# AI.net
KiCad netlist of a schematic drawn in Altium Designer
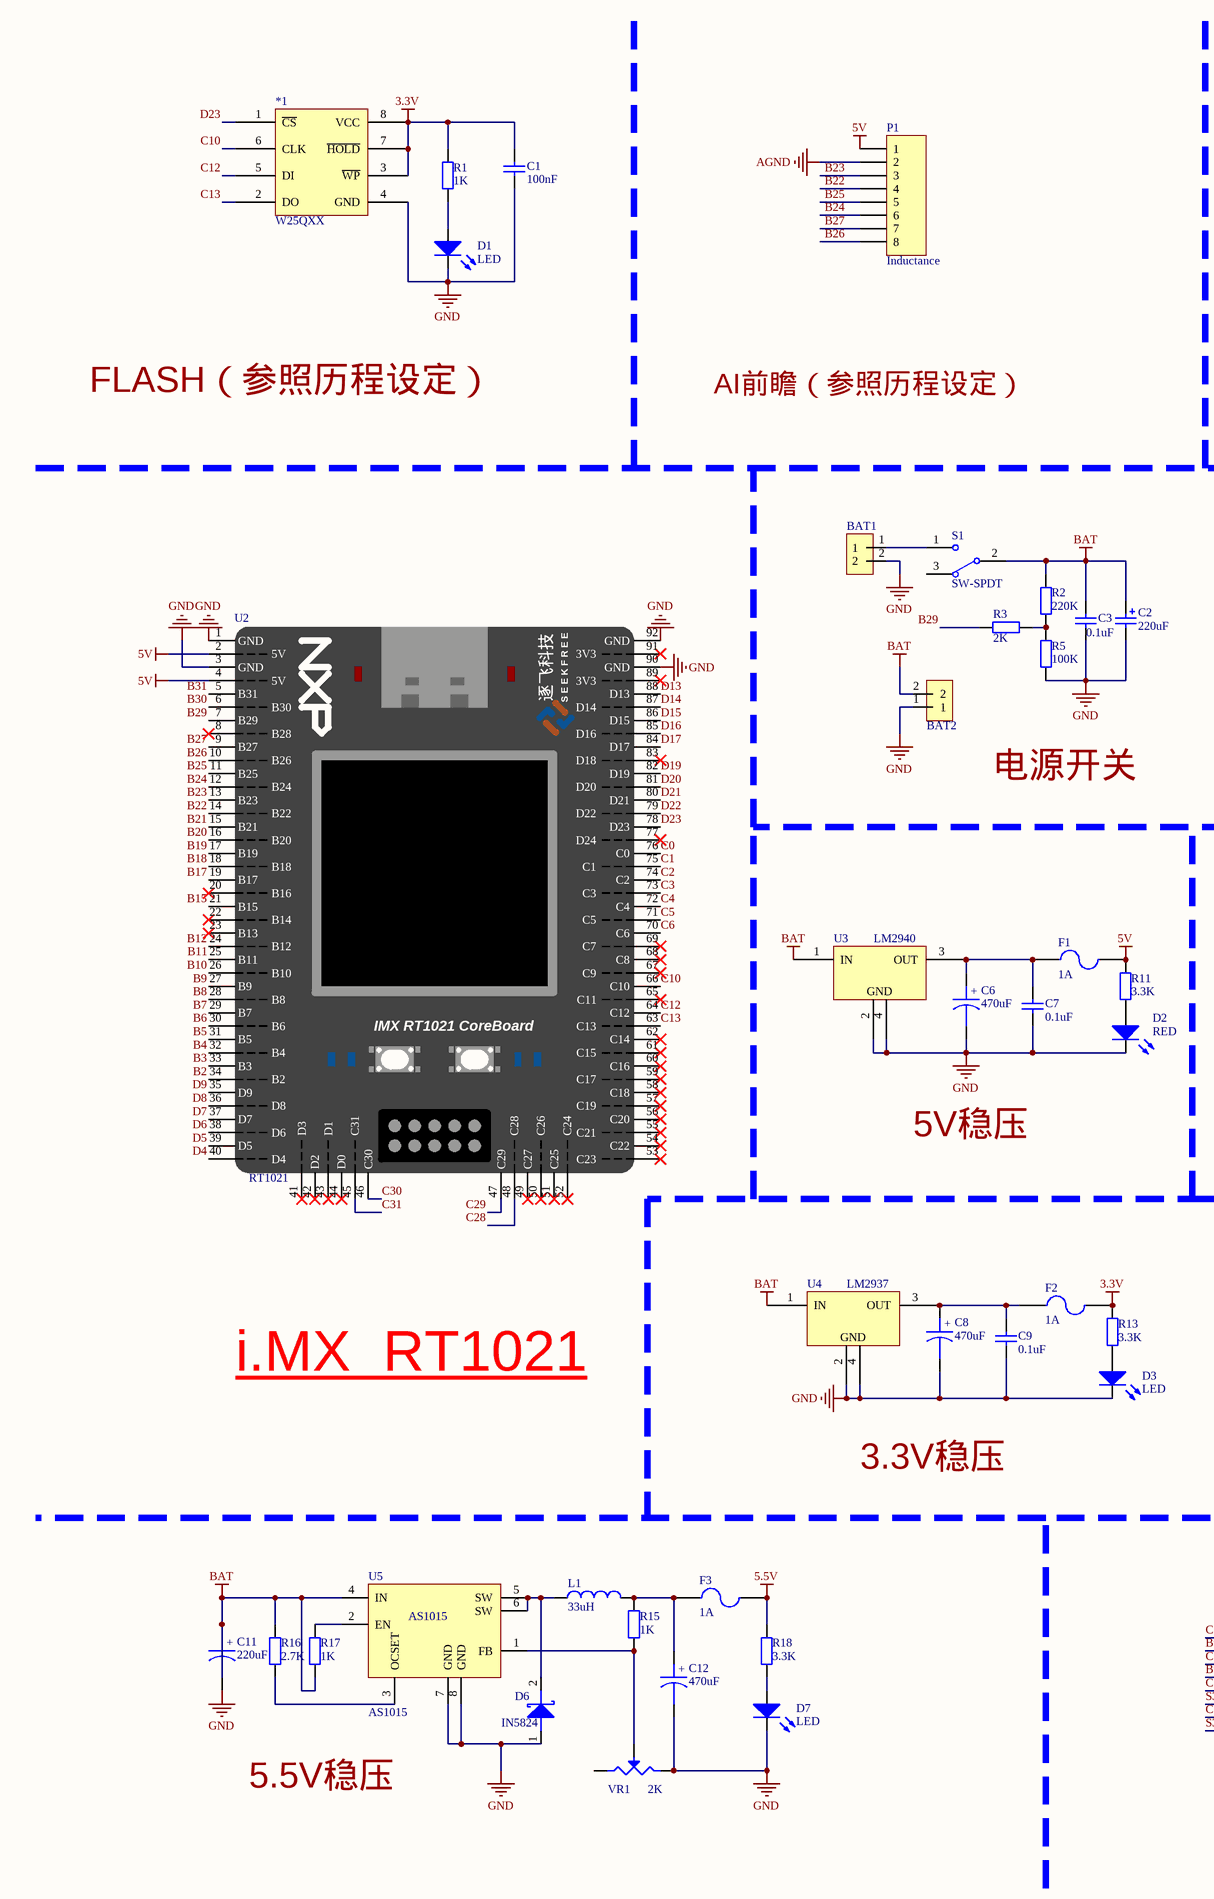
[diagram p0: AI原理图.SchDoc, left]
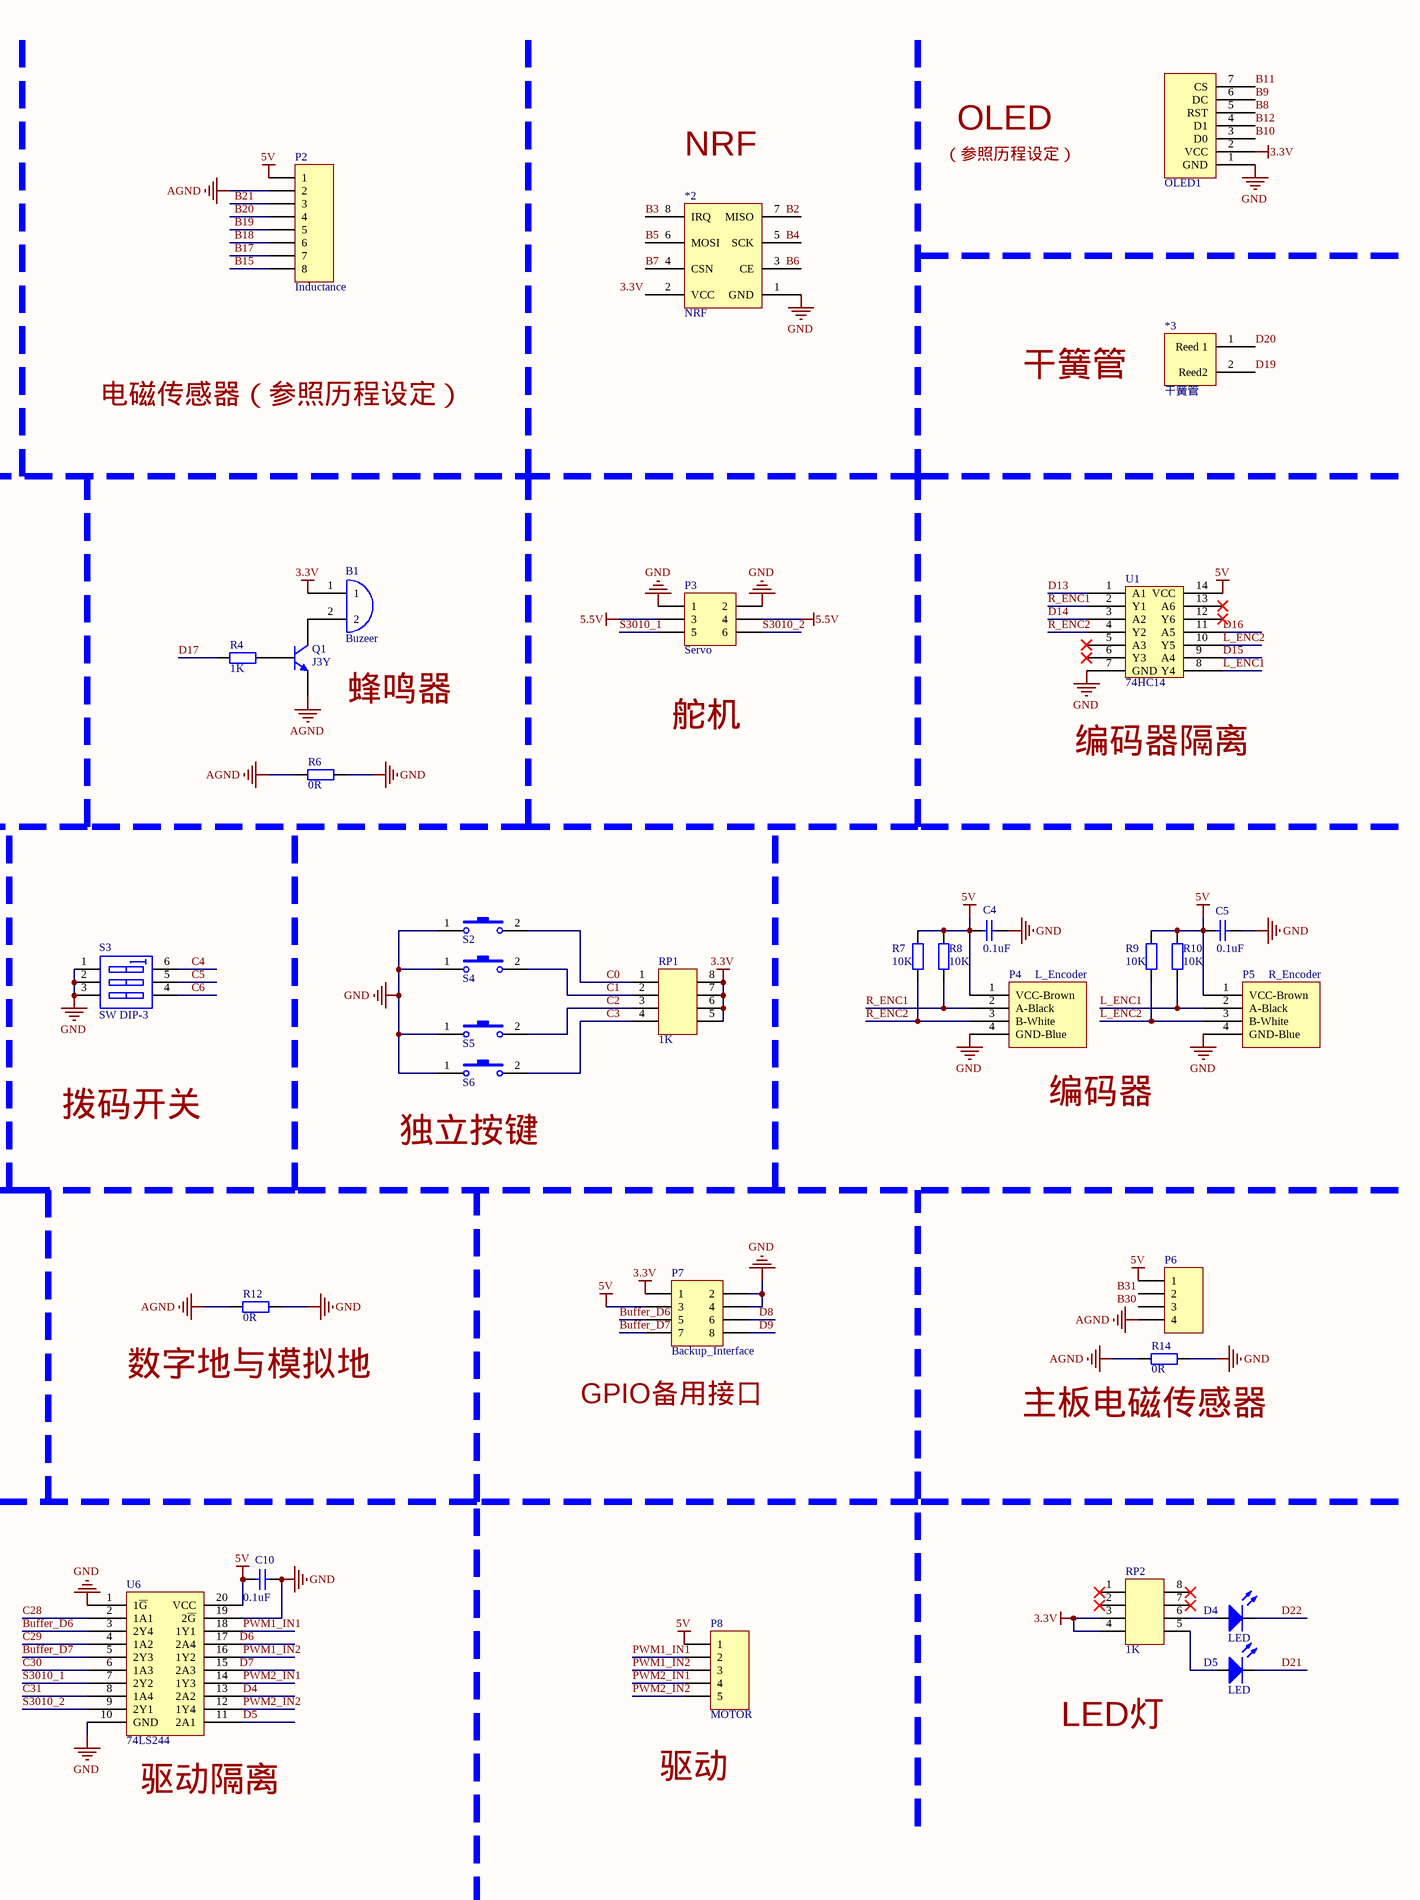
[diagram p1: AI原理图.SchDoc, right]

(export (version "E")
  (design (tool "Eeschema 10.0.6"))
  (components
    (comp (ref "*1") (value "W25QXX") (footprint "SOP8_M") (libsource (lib "红旗_SchLib_V1.0") (part "W25QXX")))
    (comp (ref "*2") (value "NRF") (footprint "HDR2X4") (libsource (lib "红旗_SchLib_V1.0") (part "NRF")))
    (comp (ref "*3") (value "干簧管") (footprint "HDR1X2") (libsource (lib "红旗_SchLib_V1.0") (part "干簧管")))
    (comp (ref "B1") (value "Buzeer") (footprint "BUZEER") (libsource (lib "红旗_SchLib") (part "Buzzer")))
    (comp (ref "BAT1")
      (value "电池")
      (footprint "PIN2")
      (description "Jumper")
      (libsource (lib "") (part "Header 2_1"))
    )
    (comp (ref "BAT2")
      (value "驱动")
      (footprint "T")
      (description "Jumper")
      (libsource (lib "红旗_SchLib") (part "Header 2"))
    )
    (comp (ref "C1")
      (value "100nF")
      (footprint "0805C")
      (description "Capacitor (Semiconductor SIM Model)")
      (fields (field (name "PUBLISHER") "Altium Limited"))
      (libsource (lib "红旗_SchLib") (part "Cap Semi"))
    )
    (comp (ref "C2")
      (value "220uF")
      (footprint "直插电解电容")
      (description "Polarized Capacitor (Radial)")
      (fields (field (name "PUBLISHER") "Altium Limited"))
      (libsource (lib "红旗_SchLib") (part "Cap Pol1"))
    )
    (comp (ref "C3")
      (value "0.1uF")
      (footprint "0805C")
      (description "Capacitor (Semiconductor SIM Model)")
      (fields (field (name "PUBLISHER") "Altium Limited"))
      (libsource (lib "红旗_SchLib") (part "Cap Semi"))
    )
    (comp (ref "C4")
      (value "0.1uF")
      (footprint "0805C")
      (description "Capacitor (Semiconductor SIM Model)")
      (fields (field (name "PUBLISHER") "Altium Limited"))
      (libsource (lib "PCB_Project2") (part "Cap Semi"))
    )
    (comp (ref "C5")
      (value "0.1uF")
      (footprint "0805C")
      (description "Capacitor (Semiconductor SIM Model)")
      (fields (field (name "PUBLISHER") "Altium Limited"))
      (libsource (lib "PCB_Project2") (part "Cap Semi"))
    )
    (comp (ref "C6")
      (value "470uF")
      (footprint "LQ_C10X10")
      (description "Capacitor")
      (libsource (lib "红旗_SchLib") (part "CAPACITOR POL"))
    )
    (comp (ref "C7")
      (value "0.1uF")
      (footprint "0805C")
      (description "Capacitor (Semiconductor SIM Model)")
      (fields (field (name "PUBLISHER") "Altium Limited"))
      (libsource (lib "红旗_SchLib") (part "Cap Semi"))
    )
    (comp (ref "C8")
      (value "470uF")
      (footprint "LQ_C10X10")
      (description "Capacitor")
      (libsource (lib "红旗_SchLib") (part "CAPACITOR POL"))
    )
    (comp (ref "C9")
      (value "0.1uF")
      (footprint "0805C")
      (description "Capacitor (Semiconductor SIM Model)")
      (fields (field (name "PUBLISHER") "Altium Limited"))
      (libsource (lib "红旗_SchLib") (part "Cap Semi"))
    )
    (comp (ref "C10")
      (value "0.1uF")
      (footprint "0805C")
      (description "Capacitor (Semiconductor SIM Model)")
      (fields (field (name "PUBLISHER") "Altium Limited"))
      (libsource (lib "PCB_Project2") (part "Cap Semi"))
    )
    (comp (ref "C11")
      (value "220uF")
      (footprint "直插电解电容")
      (description "Capacitor")
      (libsource (lib "红旗_SchLib") (part "CAPACITOR POL"))
    )
    (comp (ref "C12")
      (value "470uF")
      (footprint "LQ_C10X10")
      (description "Capacitor")
      (libsource (lib "红旗_SchLib") (part "CAPACITOR POL"))
    )
    (comp (ref "D1")
      (value "LED")
      (footprint "LED0805R")
      (description "Typical RED, GREEN, YELLOW, AMBER GaAs LED")
      (fields (field (name "PUBLISHER") "Altium Limited"))
      (libsource (lib "红旗_SchLib") (part "LED2"))
    )
    (comp (ref "D2")
      (value "RED")
      (footprint "LED0805R")
      (description "Typical RED, GREEN, YELLOW, AMBER GaAs LED")
      (fields (field (name "PUBLISHER") "Altium Limited"))
      (libsource (lib "红旗_SchLib") (part "LED2"))
    )
    (comp (ref "D3")
      (value "LED")
      (footprint "LED0805R")
      (description "Typical RED, GREEN, YELLOW, AMBER GaAs LED")
      (fields (field (name "PUBLISHER") "Altium Limited"))
      (libsource (lib "红旗_SchLib") (part "LED2"))
    )
    (comp (ref "D4")
      (value "LED")
      (footprint "LED0805R")
      (description "Typical RED, GREEN, YELLOW, AMBER GaAs LED")
      (fields (field (name "PUBLISHER") "Altium Limited"))
      (libsource (lib "红旗_SchLib") (part "LED2"))
    )
    (comp (ref "D5")
      (value "LED")
      (footprint "LED0805R")
      (description "Typical RED, GREEN, YELLOW, AMBER GaAs LED")
      (fields (field (name "PUBLISHER") "Altium Limited"))
      (libsource (lib "红旗_SchLib") (part "LED2"))
    )
    (comp (ref "D6")
      (value "IN5824")
      (footprint "SMA")
      (description "MBRA140T3")
      (libsource (lib "红旗_SchLib") (part "D-MBRA140T3"))
    )
    (comp (ref "D7")
      (value "LED")
      (footprint "LED0805R")
      (description "Typical RED, GREEN, YELLOW, AMBER GaAs LED")
      (fields (field (name "PUBLISHER") "Altium Limited"))
      (libsource (lib "红旗_SchLib") (part "LED2"))
    )
    (comp (ref "F1")
      (value "1A")
      (footprint "C1206")
      (description "Fuse")
      (fields (field (name "PUBLISHER") "Altium Limited"))
      (libsource (lib "红旗_SchLib") (part "Fuse 2"))
    )
    (comp (ref "F2")
      (value "1A")
      (footprint "C1206")
      (description "Fuse")
      (fields (field (name "PUBLISHER") "Altium Limited"))
      (libsource (lib "红旗_SchLib") (part "Fuse 2"))
    )
    (comp (ref "F3")
      (value "1A")
      (footprint "C1206")
      (description "Fuse")
      (fields (field (name "PUBLISHER") "Altium Limited"))
      (libsource (lib "红旗_SchLib") (part "Fuse 2"))
    )
    (comp (ref "L1") (value "33uH") (footprint "L7*7") (libsource (lib "红旗_SchLib") (part "Inductor")))
    (comp (ref "OLED1")
      (value "OLED128X64")
      (footprint "OLED128x64")
      (libsource (lib "红旗_SchLib") (part "OLED128X64"))
    )
    (comp (ref "P1")
      (value "Inductance")
      (footprint "HDR1X8")
      (description "Header, 8-Pin")
      (fields (field (name "PUBLISHER") "Altium Limited"))
      (libsource (lib "Miscellaneous Connectors") (part "Header 8"))
    )
    (comp (ref "P2")
      (value "Inductance")
      (footprint "HDR1X8")
      (description "Header, 8-Pin")
      (fields (field (name "PUBLISHER") "Altium Limited"))
      (libsource (lib "Miscellaneous Connectors") (part "Header 8"))
    )
    (comp (ref "P3")
      (value "Servo")
      (footprint "HDR2X3")
      (description "Header, 3-Pin, Dual row")
      (fields (field (name "PUBLISHER") "Altium Limited"))
      (libsource (lib "红旗_SchLib_V1.0") (part "Header 3X2"))
    )
    (comp (ref "P4") (value "L_Encoder") (footprint "4针凹槽") (libsource (lib "PCB_Project2") (part "COODER")))
    (comp (ref "P5") (value "R_Encoder") (footprint "4针凹槽") (libsource (lib "PCB_Project2") (part "COODER")))
    (comp (ref "P6")
      (value "Header 4")
      (footprint "HDR1X4")
      (description "Header, 4-Pin")
      (fields (field (name "PUBLISHER") "Altium Limited"))
      (libsource (lib "红旗_SchLib_V1.0") (part "Header 4"))
    )
    (comp (ref "P7")
      (value "Backup_Interface")
      (footprint "HDR2X4")
      (description "Header, 4-Pin, Dual row")
      (fields (field (name "PUBLISHER") "Altium Limited"))
      (libsource (lib "红旗_SchLib") (part "Header 4X2"))
    )
    (comp (ref "P8")
      (value "MOTOR")
      (footprint "HDR1X5")
      (description "Header, 5-Pin")
      (fields (field (name "PUBLISHER") "Altium Limited"))
      (libsource (lib "红旗_SchLib") (part "Header 5"))
    )
    (comp (ref "Q1")
      (value "J3Y")
      (footprint "SOT23-3N")
      (description "NPN Bipolar Transistor")
      (fields (field (name "PUBLISHER") "Altium Limited"))
      (libsource (lib "红旗_SchLib") (part "NPN"))
    )
    (comp (ref "R1")
      (value "1K")
      (footprint "0805-1R")
      (description "Resistor")
      (fields (field (name "PUBLISHER") "Altium Limited"))
      (libsource (lib "") (part "Res2_1"))
    )
    (comp (ref "R2")
      (value "220K")
      (footprint "0805-1R")
      (description "Resistor")
      (fields (field (name "PUBLISHER") "Altium Limited"))
      (libsource (lib "") (part "Res2_1"))
    )
    (comp (ref "R3")
      (value "2K")
      (footprint "0805-1R")
      (description "Resistor")
      (fields (field (name "PUBLISHER") "Altium Limited"))
      (libsource (lib "") (part "Res2_2"))
    )
    (comp (ref "R4")
      (value "1K")
      (footprint "0805-1R")
      (description "Resistor")
      (fields (field (name "PUBLISHER") "Altium Limited"))
      (libsource (lib "红旗_SchLib") (part "Res2"))
    )
    (comp (ref "R5")
      (value "100K")
      (footprint "0805-1R")
      (description "Resistor")
      (fields (field (name "PUBLISHER") "Altium Limited"))
      (libsource (lib "") (part "Res2_1"))
    )
    (comp (ref "R6")
      (value "0R")
      (footprint "0805-1R")
      (description "Resistor")
      (fields (field (name "PUBLISHER") "Altium Limited"))
      (libsource (lib "红旗_SchLib") (part "Res2"))
    )
    (comp (ref "R7")
      (value "10K")
      (footprint "0805-1R")
      (description "Resistor")
      (fields (field (name "PUBLISHER") "Altium Limited"))
      (libsource (lib "Miscellaneous Devices") (part "Res2"))
    )
    (comp (ref "R8")
      (value "10K")
      (footprint "0805-1R")
      (description "Resistor")
      (fields (field (name "PUBLISHER") "Altium Limited"))
      (libsource (lib "Miscellaneous Devices") (part "Res2"))
    )
    (comp (ref "R9")
      (value "10K")
      (footprint "0805-1R")
      (description "Resistor")
      (fields (field (name "PUBLISHER") "Altium Limited"))
      (libsource (lib "Miscellaneous Devices") (part "Res2"))
    )
    (comp (ref "R10")
      (value "10K")
      (footprint "0805-1R")
      (description "Resistor")
      (fields (field (name "PUBLISHER") "Altium Limited"))
      (libsource (lib "Miscellaneous Devices") (part "Res2"))
    )
    (comp (ref "R11")
      (value "3.3K")
      (footprint "0805-1R")
      (description "Resistor")
      (fields (field (name "PUBLISHER") "Altium Limited"))
      (libsource (lib "") (part "Res2_1"))
    )
    (comp (ref "R12")
      (value "0R")
      (footprint "0805-1R")
      (description "Resistor")
      (fields (field (name "PUBLISHER") "Altium Limited"))
      (libsource (lib "红旗_SchLib") (part "Res2"))
    )
    (comp (ref "R13")
      (value "3.3K")
      (footprint "0805-1R")
      (description "Resistor")
      (fields (field (name "PUBLISHER") "Altium Limited"))
      (libsource (lib "") (part "Res2_1"))
    )
    (comp (ref "R14")
      (value "0R")
      (footprint "0805-1R")
      (description "Resistor")
      (fields (field (name "PUBLISHER") "Altium Limited"))
      (libsource (lib "红旗_SchLib") (part "Res2"))
    )
    (comp (ref "R15")
      (value "1K")
      (footprint "0805-1R")
      (description "Resistor")
      (fields (field (name "PUBLISHER") "Altium Limited"))
      (libsource (lib "") (part "Res2_1"))
    )
    (comp (ref "R16")
      (value "2.7K")
      (footprint "0805-1R")
      (description "Resistor")
      (fields (field (name "PUBLISHER") "Altium Limited"))
      (libsource (lib "") (part "Res2_1"))
    )
    (comp (ref "R17")
      (value "1K")
      (footprint "0805-1R")
      (description "Resistor")
      (fields (field (name "PUBLISHER") "Altium Limited"))
      (libsource (lib "") (part "Res2_1"))
    )
    (comp (ref "R18")
      (value "3.3K")
      (footprint "0805-1R")
      (description "Resistor")
      (fields (field (name "PUBLISHER") "Altium Limited"))
      (libsource (lib "") (part "Res2_1"))
    )
    (comp (ref "RP1") (value "1K") (footprint "0603_4A") (libsource (lib "红旗_SchLib") (part "B型贴片阻排—8")))
    (comp (ref "RP2") (value "1K") (footprint "0603_4A") (libsource (lib "红旗_SchLib") (part "B型贴片阻排—8")))
    (comp (ref "S1")
      (value "SW-SPDT")
      (footprint "SW-TO3")
      (description "SPDT Subminiature Toggle Switch, Right Angle Mounting, Vertical Actuation")
      (fields (field (name "PUBLISHER") "Altium Limited"))
      (libsource (lib "红旗_SchLib") (part "SW-SPDT"))
    )
    (comp (ref "S2")
      (value "SW-PB")
      (footprint "BT4SMT")
      (description "Switch")
      (fields (field (name "PUBLISHER") "Altium Limited"))
      (libsource (lib "红旗_SchLib") (part "SW-PB"))
    )
    (comp (ref "S3")
      (value "SW DIP-3")
      (footprint "SW-DIP6")
      (description "DIP Switch, 3 Position, SPST")
      (fields (field (name "PUBLISHER") "Altium Limited"))
      (libsource (lib "红旗_SchLib") (part "SW DIP-3"))
    )
    (comp (ref "S4")
      (value "SW-PB")
      (footprint "BT4SMT")
      (description "Switch")
      (fields (field (name "PUBLISHER") "Altium Limited"))
      (libsource (lib "红旗_SchLib") (part "SW-PB"))
    )
    (comp (ref "S5")
      (value "SW-PB")
      (footprint "BT4SMT")
      (description "Switch")
      (fields (field (name "PUBLISHER") "Altium Limited"))
      (libsource (lib "红旗_SchLib") (part "SW-PB"))
    )
    (comp (ref "S6")
      (value "SW-PB")
      (footprint "BT4SMT")
      (description "Switch")
      (fields (field (name "PUBLISHER") "Altium Limited"))
      (libsource (lib "红旗_SchLib") (part "SW-PB"))
    )
    (comp (ref "U1") (value "74HC14") (footprint "SOP14") (libsource (lib "红旗_SchLib") (part "74HC14")))
    (comp (ref "U2")
      (value "RT1021")
      (footprint "GAI")
      (description "逐飞科技i.MX RT1021核心板整体原理，可直接使用")
      (libsource (lib "核心板原理库") (part "MIMXRT1021xAGxA_CoreBoard"))
    )
    (comp (ref "U3")
      (value "LM2940")
      (footprint "TO263-3A")
      (libsource (lib "红旗_SchLib") (part "LM2940CT-5.0"))
    )
    (comp (ref "U4")
      (value "LM2937")
      (footprint "TO263-3A")
      (libsource (lib "红旗_SchLib") (part "LM2940CT-5.0"))
    )
    (comp (ref "U5") (value "AS1015") (footprint "SOP-8L") (libsource (lib "红旗_SchLib") (part "AS1015")))
    (comp (ref "U6") (value "74LS244") (footprint "SOP20") (libsource (lib "PCB_Project2") (part "74LS244")))
    (comp (ref "VR1") (value "2K") (footprint "3296W") (libsource (lib "红旗_SchLib") (part "R-GLIDE")))
  )
  (nets
    (net (code "1") (name "/B2") (class "Default")
      (node (ref "*2") (pin "7") (pinfunction "MISO_7") (pintype "passive"))
      (node (ref "U2") (pin "34") (pinfunction "B2_34") (pintype "passive"))
    )
    (net (code "2") (name "/B3") (class "Default")
      (node (ref "*2") (pin "8") (pinfunction "IRQ_8") (pintype "passive"))
      (node (ref "U2") (pin "33") (pinfunction "B3_33") (pintype "passive"))
    )
    (net (code "3") (name "/B4") (class "Default")
      (node (ref "*2") (pin "5") (pinfunction "SCK_5") (pintype "passive"))
      (node (ref "U2") (pin "32") (pinfunction "B4_32") (pintype "passive"))
    )
    (net (code "4") (name "/B5") (class "Default")
      (node (ref "*2") (pin "6") (pinfunction "MOSI_6") (pintype "passive"))
      (node (ref "U2") (pin "31") (pinfunction "B5_31") (pintype "passive"))
    )
    (net (code "5") (name "/B6") (class "Default")
      (node (ref "*2") (pin "3") (pinfunction "CE_3") (pintype "passive"))
      (node (ref "U2") (pin "30") (pinfunction "B6_30") (pintype "passive"))
    )
    (net (code "6") (name "/B7") (class "Default")
      (node (ref "*2") (pin "4") (pinfunction "CSN_4") (pintype "passive"))
      (node (ref "U2") (pin "29") (pinfunction "B7_29") (pintype "passive"))
    )
    (net (code "7") (name "/B8") (class "Default")
      (node (ref "OLED1") (pin "5") (pinfunction "RST_5") (pintype "passive"))
      (node (ref "U2") (pin "28") (pinfunction "B8_28") (pintype "passive"))
    )
    (net (code "8") (name "/B9") (class "Default")
      (node (ref "OLED1") (pin "6") (pinfunction "DC_6") (pintype "passive"))
      (node (ref "U2") (pin "27") (pinfunction "B9_27") (pintype "passive"))
    )
    (net (code "9") (name "/B10") (class "Default")
      (node (ref "OLED1") (pin "3") (pinfunction "D0_3") (pintype "passive"))
      (node (ref "U2") (pin "26") (pinfunction "B10_26") (pintype "passive"))
    )
    (net (code "10") (name "/B11") (class "Default")
      (node (ref "OLED1") (pin "7") (pinfunction "CS_7") (pintype "passive"))
      (node (ref "U2") (pin "25") (pinfunction "B11_25") (pintype "passive"))
    )
    (net (code "11") (name "/B12") (class "Default")
      (node (ref "OLED1") (pin "4") (pinfunction "D1_4") (pintype "passive"))
      (node (ref "U2") (pin "24") (pinfunction "B12_24") (pintype "passive"))
    )
    (net (code "12") (name "/B15") (class "Default")
      (node (ref "P2") (pin "8") (pinfunction "8_8") (pintype "passive"))
      (node (ref "U2") (pin "21") (pinfunction "B15_21") (pintype "passive"))
    )
    (net (code "13") (name "/B17") (class "Default")
      (node (ref "P2") (pin "7") (pinfunction "7_7") (pintype "passive"))
      (node (ref "U2") (pin "19") (pinfunction "B17_19") (pintype "passive"))
    )
    (net (code "14") (name "/B18") (class "Default")
      (node (ref "P2") (pin "6") (pinfunction "6_6") (pintype "passive"))
      (node (ref "U2") (pin "18") (pinfunction "B18_18") (pintype "passive"))
    )
    (net (code "15") (name "/B19") (class "Default")
      (node (ref "P2") (pin "5") (pinfunction "5_5") (pintype "passive"))
      (node (ref "U2") (pin "17") (pinfunction "B19_17") (pintype "passive"))
    )
    (net (code "16") (name "/B20") (class "Default")
      (node (ref "P2") (pin "4") (pinfunction "4_4") (pintype "passive"))
      (node (ref "U2") (pin "16") (pinfunction "B20_16") (pintype "passive"))
    )
    (net (code "17") (name "/B21") (class "Default")
      (node (ref "P2") (pin "3") (pinfunction "3_3") (pintype "passive"))
      (node (ref "U2") (pin "15") (pinfunction "B21_15") (pintype "passive"))
    )
    (net (code "18") (name "/B22") (class "Default")
      (node (ref "P1") (pin "4") (pinfunction "4_4") (pintype "passive"))
      (node (ref "U2") (pin "14") (pinfunction "B22_14") (pintype "passive"))
    )
    (net (code "19") (name "/B23") (class "Default")
      (node (ref "P1") (pin "3") (pinfunction "3_3") (pintype "passive"))
      (node (ref "U2") (pin "13") (pinfunction "B23_13") (pintype "passive"))
    )
    (net (code "20") (name "/B24") (class "Default")
      (node (ref "P1") (pin "6") (pinfunction "6_6") (pintype "passive"))
      (node (ref "U2") (pin "12") (pinfunction "B24_12") (pintype "passive"))
    )
    (net (code "21") (name "/B25") (class "Default")
      (node (ref "P1") (pin "5") (pinfunction "5_5") (pintype "passive"))
      (node (ref "U2") (pin "11") (pinfunction "B25_11") (pintype "passive"))
    )
    (net (code "22") (name "/B26") (class "Default")
      (node (ref "P1") (pin "8") (pinfunction "8_8") (pintype "passive"))
      (node (ref "U2") (pin "10") (pinfunction "B26_10") (pintype "passive"))
    )
    (net (code "23") (name "/B27") (class "Default")
      (node (ref "P1") (pin "7") (pinfunction "7_7") (pintype "passive"))
      (node (ref "U2") (pin "9") (pinfunction "B27_9") (pintype "passive"))
    )
    (net (code "24") (name "/B29") (class "Default")
      (node (ref "R3") (pin "2") (pinfunction "2_2") (pintype "passive"))
      (node (ref "U2") (pin "7") (pinfunction "B29_7") (pintype "passive"))
    )
    (net (code "25") (name "/B30") (class "Default")
      (node (ref "P6") (pin "3") (pinfunction "3_3") (pintype "passive"))
      (node (ref "U2") (pin "6") (pinfunction "B30_6") (pintype "passive"))
    )
    (net (code "26") (name "/B31") (class "Default")
      (node (ref "P6") (pin "2") (pinfunction "2_2") (pintype "passive"))
      (node (ref "U2") (pin "5") (pinfunction "B31_5") (pintype "passive"))
    )
    (net (code "27") (name "/Buffer_D6") (class "Default")
      (node (ref "P7") (pin "5") (pinfunction "5_5") (pintype "passive"))
      (node (ref "U6") (pin "3") (pinfunction "2Y4_3") (pintype "passive"))
    )
    (net (code "28") (name "/Buffer_D7") (class "Default")
      (node (ref "P7") (pin "7") (pinfunction "7_7") (pintype "passive"))
      (node (ref "U6") (pin "5") (pinfunction "2Y3_5") (pintype "passive"))
    )
    (net (code "29") (name "/C0") (class "Default")
      (node (ref "RP1") (pin "1") (pinfunction "1_1") (pintype "passive"))
      (node (ref "S2") (pin "2") (pinfunction "2_2") (pintype "passive"))
      (node (ref "U2") (pin "76") (pinfunction "C0_76") (pintype "passive"))
    )
    (net (code "30") (name "/C1") (class "Default")
      (node (ref "RP1") (pin "2") (pinfunction "2_2") (pintype "passive"))
      (node (ref "S4") (pin "2") (pinfunction "2_2") (pintype "passive"))
      (node (ref "U2") (pin "75") (pinfunction "C1_75") (pintype "passive"))
    )
    (net (code "31") (name "/C2") (class "Default")
      (node (ref "RP1") (pin "3") (pinfunction "3_3") (pintype "passive"))
      (node (ref "S5") (pin "2") (pinfunction "2_2") (pintype "passive"))
      (node (ref "U2") (pin "74") (pinfunction "C2_74") (pintype "passive"))
    )
    (net (code "32") (name "/C3") (class "Default")
      (node (ref "RP1") (pin "4") (pinfunction "4_4") (pintype "passive"))
      (node (ref "S6") (pin "2") (pinfunction "2_2") (pintype "passive"))
      (node (ref "U2") (pin "73") (pinfunction "C3_73") (pintype "passive"))
    )
    (net (code "33") (name "/C4") (class "Default")
      (node (ref "S3") (pin "6") (pinfunction "B1_6") (pintype "passive"))
      (node (ref "U2") (pin "72") (pinfunction "C4_72") (pintype "passive"))
    )
    (net (code "34") (name "/C5") (class "Default")
      (node (ref "S3") (pin "5") (pinfunction "B2_5") (pintype "passive"))
      (node (ref "U2") (pin "71") (pinfunction "C5_71") (pintype "passive"))
    )
    (net (code "35") (name "/C6") (class "Default")
      (node (ref "S3") (pin "4") (pinfunction "B3_4") (pintype "passive"))
      (node (ref "U2") (pin "70") (pinfunction "C6_70") (pintype "passive"))
    )
    (net (code "36") (name "/C10") (class "Default")
      (node (ref "*1") (pin "6") (pinfunction "CLK_6") (pintype "passive"))
      (node (ref "U2") (pin "66") (pinfunction "C10_66") (pintype "passive"))
    )
    (net (code "37") (name "/C12") (class "Default")
      (node (ref "*1") (pin "5") (pinfunction "DI_5") (pintype "passive"))
      (node (ref "U2") (pin "64") (pinfunction "C12_64") (pintype "passive"))
    )
    (net (code "38") (name "/C13") (class "Default")
      (node (ref "*1") (pin "2") (pinfunction "DO_2") (pintype "passive"))
      (node (ref "U2") (pin "63") (pinfunction "C13_63") (pintype "passive"))
    )
    (net (code "39") (name "/C28") (class "Default")
      (node (ref "U2") (pin "48") (pinfunction "C28_48") (pintype "passive"))
      (node (ref "U6") (pin "2") (pinfunction "1A1_2") (pintype "passive"))
    )
    (net (code "40") (name "/C29") (class "Default")
      (node (ref "U2") (pin "47") (pinfunction "C29_47") (pintype "passive"))
      (node (ref "U6") (pin "4") (pinfunction "1A2_4") (pintype "passive"))
    )
    (net (code "41") (name "/C30") (class "Default")
      (node (ref "U2") (pin "46") (pinfunction "C30_46") (pintype "passive"))
      (node (ref "U6") (pin "6") (pinfunction "1A3_6") (pintype "passive"))
    )
    (net (code "42") (name "/C31") (class "Default")
      (node (ref "U2") (pin "45") (pinfunction "C31_45") (pintype "passive"))
      (node (ref "U6") (pin "8") (pinfunction "1A4_8") (pintype "passive"))
    )
    (net (code "43") (name "/D4") (class "Default")
      (node (ref "U2") (pin "40") (pinfunction "D4_40") (pintype "passive"))
      (node (ref "U6") (pin "13") (pinfunction "2A2_13") (pintype "passive"))
    )
    (net (code "44") (name "/D5") (class "Default")
      (node (ref "U2") (pin "39") (pinfunction "D5_39") (pintype "passive"))
      (node (ref "U6") (pin "11") (pinfunction "2A1_11") (pintype "passive"))
    )
    (net (code "45") (name "/D6") (class "Default")
      (node (ref "U2") (pin "38") (pinfunction "D6_38") (pintype "passive"))
      (node (ref "U6") (pin "17") (pinfunction "2A4_17") (pintype "passive"))
    )
    (net (code "46") (name "/D7") (class "Default")
      (node (ref "U2") (pin "37") (pinfunction "D7_37") (pintype "passive"))
      (node (ref "U6") (pin "15") (pinfunction "2A3_15") (pintype "passive"))
    )
    (net (code "47") (name "/D8") (class "Default")
      (node (ref "P7") (pin "6") (pinfunction "6_6") (pintype "passive"))
      (node (ref "U2") (pin "36") (pinfunction "D8_36") (pintype "passive"))
    )
    (net (code "48") (name "/D9") (class "Default")
      (node (ref "P7") (pin "8") (pinfunction "8_8") (pintype "passive"))
      (node (ref "U2") (pin "35") (pinfunction "D9_35") (pintype "passive"))
    )
    (net (code "49") (name "/D13") (class "Default")
      (node (ref "U1") (pin "1") (pinfunction "A1_1") (pintype "passive"))
      (node (ref "U2") (pin "88") (pinfunction "D13_88") (pintype "passive"))
    )
    (net (code "50") (name "/D14") (class "Default")
      (node (ref "U1") (pin "3") (pinfunction "A2_3") (pintype "passive"))
      (node (ref "U2") (pin "87") (pinfunction "D14_87") (pintype "passive"))
    )
    (net (code "51") (name "/D15") (class "Default")
      (node (ref "U1") (pin "9") (pinfunction "A4_9") (pintype "passive"))
      (node (ref "U2") (pin "86") (pinfunction "D15_86") (pintype "passive"))
    )
    (net (code "52") (name "/D16") (class "Default")
      (node (ref "U1") (pin "11") (pinfunction "A5_11") (pintype "passive"))
      (node (ref "U2") (pin "85") (pinfunction "D16_85") (pintype "passive"))
    )
    (net (code "53") (name "/D17") (class "Default")
      (node (ref "R4") (pin "1") (pinfunction "1_1") (pintype "passive"))
      (node (ref "U2") (pin "84") (pinfunction "D17_84") (pintype "passive"))
    )
    (net (code "54") (name "/D19") (class "Default")
      (node (ref "*3") (pin "2") (pinfunction "Reed2_2") (pintype "passive"))
      (node (ref "U2") (pin "82") (pinfunction "D19_82") (pintype "passive"))
    )
    (net (code "55") (name "/D20") (class "Default")
      (node (ref "*3") (pin "1") (pinfunction "Reed_1_1") (pintype "passive"))
      (node (ref "U2") (pin "81") (pinfunction "D20_81") (pintype "passive"))
    )
    (net (code "56") (name "/D21") (class "Default")
      (node (ref "D5") (pin "2") (pinfunction "K_2") (pintype "passive"))
      (node (ref "U2") (pin "80") (pinfunction "D21_80") (pintype "passive"))
    )
    (net (code "57") (name "/D22") (class "Default")
      (node (ref "D4") (pin "2") (pinfunction "K_2") (pintype "passive"))
      (node (ref "U2") (pin "79") (pinfunction "D22_79") (pintype "passive"))
    )
    (net (code "58") (name "/D23") (class "Default")
      (node (ref "*1") (pin "1") (pinfunction "~{CS}_1") (pintype "passive"))
      (node (ref "U2") (pin "78") (pinfunction "D23_78") (pintype "passive"))
    )
    (net (code "59") (name "/L_ENC1") (class "Default")
      (node (ref "P5") (pin "2") (pinfunction "A-Black_2") (pintype "passive"))
      (node (ref "R10") (pin "1") (pinfunction "1_1") (pintype "passive"))
      (node (ref "U1") (pin "8") (pinfunction "Y4_8") (pintype "passive"))
    )
    (net (code "60") (name "/L_ENC2") (class "Default")
      (node (ref "P5") (pin "3") (pinfunction "B-White_3") (pintype "passive"))
      (node (ref "R9") (pin "1") (pinfunction "1_1") (pintype "passive"))
      (node (ref "U1") (pin "10") (pinfunction "Y5_10") (pintype "passive"))
    )
    (net (code "61") (name "/PWM1_IN1") (class "Default")
      (node (ref "P8") (pin "2") (pinfunction "2_2") (pintype "passive"))
      (node (ref "U6") (pin "18") (pinfunction "1Y1_18") (pintype "passive"))
    )
    (net (code "62") (name "/PWM1_IN2") (class "Default")
      (node (ref "P8") (pin "3") (pinfunction "3_3") (pintype "passive"))
      (node (ref "U6") (pin "16") (pinfunction "1Y2_16") (pintype "passive"))
    )
    (net (code "63") (name "/PWM2_IN1") (class "Default")
      (node (ref "P8") (pin "4") (pinfunction "4_4") (pintype "passive"))
      (node (ref "U6") (pin "14") (pinfunction "1Y3_14") (pintype "passive"))
    )
    (net (code "64") (name "/PWM2_IN2") (class "Default")
      (node (ref "P8") (pin "5") (pinfunction "5_5") (pintype "passive"))
      (node (ref "U6") (pin "12") (pinfunction "1Y4_12") (pintype "passive"))
    )
    (net (code "65") (name "/R_ENC1") (class "Default")
      (node (ref "P4") (pin "2") (pinfunction "A-Black_2") (pintype "passive"))
      (node (ref "R8") (pin "1") (pinfunction "1_1") (pintype "passive"))
      (node (ref "U1") (pin "2") (pinfunction "Y1_2") (pintype "passive"))
    )
    (net (code "66") (name "/R_ENC2") (class "Default")
      (node (ref "P4") (pin "3") (pinfunction "B-White_3") (pintype "passive"))
      (node (ref "R7") (pin "1") (pinfunction "1_1") (pintype "passive"))
      (node (ref "U1") (pin "4") (pinfunction "Y2_4") (pintype "passive"))
    )
    (net (code "67") (name "/S3010_1") (class "Default")
      (node (ref "P3") (pin "5") (pinfunction "5_5") (pintype "passive"))
      (node (ref "U6") (pin "7") (pinfunction "2Y2_7") (pintype "passive"))
    )
    (net (code "68") (name "/S3010_2") (class "Default")
      (node (ref "P3") (pin "6") (pinfunction "6_6") (pintype "passive"))
      (node (ref "U6") (pin "9") (pinfunction "2Y1_9") (pintype "passive"))
    )
    (net (code "69") (name "3.3V") (class "Default")
      (node (ref "*1") (pin "3") (pinfunction "~{WP}_3") (pintype "passive"))
      (node (ref "*1") (pin "7") (pinfunction "~{HOLD}_7") (pintype "passive"))
      (node (ref "*1") (pin "8") (pinfunction "VCC_8") (pintype "passive"))
      (node (ref "*2") (pin "2") (pinfunction "VCC_2") (pintype "passive"))
      (node (ref "B1") (pin "1") (pinfunction "1_1") (pintype "passive"))
      (node (ref "C1") (pin "1") (pinfunction "1_1") (pintype "passive"))
      (node (ref "F2") (pin "2") (pinfunction "2_2") (pintype "passive"))
      (node (ref "OLED1") (pin "2") (pinfunction "VCC_2") (pintype "passive"))
      (node (ref "P7") (pin "1") (pinfunction "1_1") (pintype "passive"))
      (node (ref "R1") (pin "2") (pinfunction "2_2") (pintype "passive"))
      (node (ref "R13") (pin "2") (pinfunction "2_2") (pintype "passive"))
      (node (ref "RP1") (pin "5") (pinfunction "5_5") (pintype "passive"))
      (node (ref "RP1") (pin "6") (pinfunction "6_6") (pintype "passive"))
      (node (ref "RP1") (pin "7") (pinfunction "7_7") (pintype "passive"))
      (node (ref "RP1") (pin "8") (pinfunction "8_8") (pintype "passive"))
      (node (ref "RP2") (pin "3") (pinfunction "3_3") (pintype "passive"))
      (node (ref "RP2") (pin "4") (pinfunction "4_4") (pintype "passive"))
    )
    (net (code "70") (name "5.5V") (class "Default")
      (node (ref "F3") (pin "2") (pinfunction "2_2") (pintype "passive"))
      (node (ref "P3") (pin "3") (pinfunction "3_3") (pintype "passive"))
      (node (ref "P3") (pin "4") (pinfunction "4_4") (pintype "passive"))
      (node (ref "R18") (pin "2") (pinfunction "2_2") (pintype "passive"))
    )
    (net (code "71") (name "5V") (class "Default")
      (node (ref "C10") (pin "1") (pinfunction "1_1") (pintype "passive"))
      (node (ref "C4") (pin "1") (pinfunction "1_1") (pintype "passive"))
      (node (ref "C5") (pin "1") (pinfunction "1_1") (pintype "passive"))
      (node (ref "F1") (pin "2") (pinfunction "2_2") (pintype "passive"))
      (node (ref "P1") (pin "1") (pinfunction "1_1") (pintype "passive"))
      (node (ref "P2") (pin "1") (pinfunction "1_1") (pintype "passive"))
      (node (ref "P4") (pin "1") (pinfunction "VCC-Brown_1") (pintype "passive"))
      (node (ref "P5") (pin "1") (pinfunction "VCC-Brown_1") (pintype "passive"))
      (node (ref "P6") (pin "1") (pinfunction "1_1") (pintype "passive"))
      (node (ref "P7") (pin "3") (pinfunction "3_3") (pintype "passive"))
      (node (ref "P8") (pin "1") (pinfunction "1_1") (pintype "passive"))
      (node (ref "R10") (pin "2") (pinfunction "2_2") (pintype "passive"))
      (node (ref "R11") (pin "2") (pinfunction "2_2") (pintype "passive"))
      (node (ref "R7") (pin "2") (pinfunction "2_2") (pintype "passive"))
      (node (ref "R8") (pin "2") (pinfunction "2_2") (pintype "passive"))
      (node (ref "R9") (pin "2") (pinfunction "2_2") (pintype "passive"))
      (node (ref "U1") (pin "14") (pinfunction "VCC_14") (pintype "passive"))
      (node (ref "U2") (pin "2") (pinfunction "5V_2") (pintype "passive"))
      (node (ref "U2") (pin "4") (pinfunction "5V_4") (pintype "passive"))
      (node (ref "U6") (pin "20") (pinfunction "VCC_20") (pintype "passive"))
    )
    (net (code "72") (name "AGND") (class "Default")
      (node (ref "P1") (pin "2") (pinfunction "2_2") (pintype "passive"))
      (node (ref "P2") (pin "2") (pinfunction "2_2") (pintype "passive"))
      (node (ref "P6") (pin "4") (pinfunction "4_4") (pintype "passive"))
      (node (ref "Q1") (pin "3") (pinfunction "E_3") (pintype "passive"))
      (node (ref "R12") (pin "1") (pinfunction "1_1") (pintype "passive"))
      (node (ref "R14") (pin "1") (pinfunction "1_1") (pintype "passive"))
      (node (ref "R6") (pin "1") (pinfunction "1_1") (pintype "passive"))
    )
    (net (code "73") (name "BAT") (class "Default")
      (node (ref "BAT2") (pin "2") (pinfunction "2_2") (pintype "passive"))
      (node (ref "C11") (pin "1") (pinfunction "1_1") (pintype "passive"))
      (node (ref "C2") (pin "1") (pinfunction "1_1") (pintype "passive"))
      (node (ref "C3") (pin "2") (pinfunction "2_2") (pintype "passive"))
      (node (ref "R16") (pin "2") (pinfunction "2_2") (pintype "passive"))
      (node (ref "R17") (pin "1") (pinfunction "1_1") (pintype "passive"))
      (node (ref "R2") (pin "2") (pinfunction "2_2") (pintype "passive"))
      (node (ref "S1") (pin "2") (pinfunction "2_2") (pintype "passive"))
      (node (ref "U3") (pin "1") (pinfunction "IN_1") (pintype "passive"))
      (node (ref "U4") (pin "1") (pinfunction "IN_1") (pintype "passive"))
      (node (ref "U5") (pin "4") (pinfunction "IN_4") (pintype "passive"))
    )
    (net (code "74") (name "GND") (class "Default")
      (node (ref "*1") (pin "4") (pinfunction "GND_4") (pintype "passive"))
      (node (ref "*2") (pin "1") (pinfunction "GND_1") (pintype "passive"))
      (node (ref "BAT1") (pin "2") (pinfunction "2_2") (pintype "passive"))
      (node (ref "BAT2") (pin "1") (pinfunction "1_1") (pintype "passive"))
      (node (ref "C1") (pin "2") (pinfunction "2_2") (pintype "passive"))
      (node (ref "C10") (pin "2") (pinfunction "2_2") (pintype "passive"))
      (node (ref "C11") (pin "2") (pinfunction "2_2") (pintype "passive"))
      (node (ref "C12") (pin "2") (pinfunction "2_2") (pintype "passive"))
      (node (ref "C2") (pin "2") (pinfunction "2_2") (pintype "passive"))
      (node (ref "C3") (pin "1") (pinfunction "1_1") (pintype "passive"))
      (node (ref "C4") (pin "2") (pinfunction "2_2") (pintype "passive"))
      (node (ref "C5") (pin "2") (pinfunction "2_2") (pintype "passive"))
      (node (ref "C6") (pin "2") (pinfunction "2_2") (pintype "passive"))
      (node (ref "C7") (pin "1") (pinfunction "1_1") (pintype "passive"))
      (node (ref "C8") (pin "2") (pinfunction "2_2") (pintype "passive"))
      (node (ref "C9") (pin "1") (pinfunction "1_1") (pintype "passive"))
      (node (ref "D1") (pin "2") (pinfunction "K_2") (pintype "passive"))
      (node (ref "D2") (pin "2") (pinfunction "K_2") (pintype "passive"))
      (node (ref "D3") (pin "2") (pinfunction "K_2") (pintype "passive"))
      (node (ref "D6") (pin "1") (pinfunction "1_1") (pintype "passive"))
      (node (ref "D7") (pin "2") (pinfunction "K_2") (pintype "passive"))
      (node (ref "OLED1") (pin "1") (pinfunction "GND_1") (pintype "passive"))
      (node (ref "P3") (pin "1") (pinfunction "1_1") (pintype "passive"))
      (node (ref "P3") (pin "2") (pinfunction "2_2") (pintype "passive"))
      (node (ref "P4") (pin "4") (pinfunction "GND-Blue_4") (pintype "passive"))
      (node (ref "P5") (pin "4") (pinfunction "GND-Blue_4") (pintype "passive"))
      (node (ref "P7") (pin "2") (pinfunction "2_2") (pintype "passive"))
      (node (ref "P7") (pin "4") (pinfunction "4_4") (pintype "passive"))
      (node (ref "R12") (pin "2") (pinfunction "2_2") (pintype "passive"))
      (node (ref "R14") (pin "2") (pinfunction "2_2") (pintype "passive"))
      (node (ref "R5") (pin "1") (pinfunction "1_1") (pintype "passive"))
      (node (ref "R6") (pin "2") (pinfunction "2_2") (pintype "passive"))
      (node (ref "S2") (pin "1") (pinfunction "1_1") (pintype "passive"))
      (node (ref "S3") (pin "1") (pinfunction "A1_1") (pintype "passive"))
      (node (ref "S3") (pin "2") (pinfunction "A2_2") (pintype "passive"))
      (node (ref "S3") (pin "3") (pinfunction "A3_3") (pintype "passive"))
      (node (ref "S4") (pin "1") (pinfunction "1_1") (pintype "passive"))
      (node (ref "S5") (pin "1") (pinfunction "1_1") (pintype "passive"))
      (node (ref "S6") (pin "1") (pinfunction "1_1") (pintype "passive"))
      (node (ref "U1") (pin "7") (pinfunction "GND_7") (pintype "passive"))
      (node (ref "U2") (pin "1") (pinfunction "GND_1") (pintype "passive"))
      (node (ref "U2") (pin "3") (pinfunction "GND_3") (pintype "passive"))
      (node (ref "U2") (pin "90") (pinfunction "GND_90") (pintype "passive"))
      (node (ref "U2") (pin "92") (pinfunction "GND_92") (pintype "passive"))
      (node (ref "U3") (pin "2") (pinfunction "GND_2") (pintype "passive"))
      (node (ref "U3") (pin "4") (pinfunction "GND_4") (pintype "passive"))
      (node (ref "U4") (pin "2") (pinfunction "GND_2") (pintype "passive"))
      (node (ref "U4") (pin "4") (pinfunction "GND_4") (pintype "passive"))
      (node (ref "U5") (pin "7") (pinfunction "GND_7") (pintype "passive"))
      (node (ref "U5") (pin "8") (pinfunction "GND_8") (pintype "passive"))
      (node (ref "U6") (pin "1") (pinfunction "1~{G}_1") (pintype "passive"))
      (node (ref "U6") (pin "10") (pinfunction "GND_10") (pintype "passive"))
      (node (ref "U6") (pin "19") (pinfunction "2~{G}_19") (pintype "passive"))
      (node (ref "VR1") (pin "2") (pinfunction "2_2") (pintype "passive"))
    )
    (net (code "75") (name "Net-(BAT1-Pad1)") (class "Default")
      (node (ref "BAT1") (pin "1") (pinfunction "1_1") (pintype "passive"))
      (node (ref "S1") (pin "1") (pinfunction "1_1") (pintype "passive"))
    )
    (net (code "76") (name "Net-(C12-Pad1)") (class "Default")
      (node (ref "C12") (pin "1") (pinfunction "1_1") (pintype "passive"))
      (node (ref "F3") (pin "1") (pinfunction "1_1") (pintype "passive"))
      (node (ref "L1") (pin "2") (pinfunction "2_2") (pintype "passive"))
      (node (ref "R15") (pin "2") (pinfunction "2_2") (pintype "passive"))
    )
    (net (code "77") (name "Net-(D1-A)") (class "Default")
      (node (ref "D1") (pin "1") (pinfunction "A_1") (pintype "passive"))
      (node (ref "R1") (pin "1") (pinfunction "1_1") (pintype "passive"))
    )
    (net (code "78") (name "Net-(D2-A)") (class "Default")
      (node (ref "D2") (pin "1") (pinfunction "A_1") (pintype "passive"))
      (node (ref "R11") (pin "1") (pinfunction "1_1") (pintype "passive"))
    )
    (net (code "79") (name "Net-(D3-A)") (class "Default")
      (node (ref "D3") (pin "1") (pinfunction "A_1") (pintype "passive"))
      (node (ref "R13") (pin "1") (pinfunction "1_1") (pintype "passive"))
    )
    (net (code "80") (name "Net-(D4-A)") (class "Default")
      (node (ref "D4") (pin "1") (pinfunction "A_1") (pintype "passive"))
      (node (ref "RP2") (pin "6") (pinfunction "6_6") (pintype "passive"))
    )
    (net (code "81") (name "Net-(D5-A)") (class "Default")
      (node (ref "D5") (pin "1") (pinfunction "A_1") (pintype "passive"))
      (node (ref "RP2") (pin "5") (pinfunction "5_5") (pintype "passive"))
    )
    (net (code "82") (name "Net-(D6-Pad2)") (class "Default")
      (node (ref "D6") (pin "2") (pinfunction "2_2") (pintype "passive"))
      (node (ref "L1") (pin "1") (pinfunction "1_1") (pintype "passive"))
      (node (ref "U5") (pin "5") (pinfunction "SW_5") (pintype "passive"))
      (node (ref "U5") (pin "6") (pinfunction "SW_6") (pintype "passive"))
    )
    (net (code "83") (name "Net-(D7-A)") (class "Default")
      (node (ref "D7") (pin "1") (pinfunction "A_1") (pintype "passive"))
      (node (ref "R18") (pin "1") (pinfunction "1_1") (pintype "passive"))
    )
    (net (code "84") (name "Net-(Q1-B)") (class "Default")
      (node (ref "Q1") (pin "2") (pinfunction "B_2") (pintype "passive"))
      (node (ref "R4") (pin "2") (pinfunction "2_2") (pintype "passive"))
    )
    (net (code "85") (name "Net-(Q1-C)") (class "Default")
      (node (ref "B1") (pin "2") (pinfunction "2_2") (pintype "passive"))
      (node (ref "Q1") (pin "1") (pinfunction "C_1") (pintype "passive"))
    )
    (net (code "86") (name "Net-(R2-Pad1)") (class "Default")
      (node (ref "R2") (pin "1") (pinfunction "1_1") (pintype "passive"))
      (node (ref "R3") (pin "1") (pinfunction "1_1") (pintype "passive"))
      (node (ref "R5") (pin "2") (pinfunction "2_2") (pintype "passive"))
    )
    (net (code "87") (name "Net-(U3-OUT)") (class "Default")
      (node (ref "C6") (pin "1") (pinfunction "1_1") (pintype "passive"))
      (node (ref "C7") (pin "2") (pinfunction "2_2") (pintype "passive"))
      (node (ref "F1") (pin "1") (pinfunction "1_1") (pintype "passive"))
      (node (ref "U3") (pin "3") (pinfunction "OUT_3") (pintype "passive"))
    )
    (net (code "88") (name "Net-(U4-OUT)") (class "Default")
      (node (ref "C8") (pin "1") (pinfunction "1_1") (pintype "passive"))
      (node (ref "C9") (pin "2") (pinfunction "2_2") (pintype "passive"))
      (node (ref "F2") (pin "1") (pinfunction "1_1") (pintype "passive"))
      (node (ref "U4") (pin "3") (pinfunction "OUT_3") (pintype "passive"))
    )
    (net (code "89") (name "Net-(U5-EN)") (class "Default")
      (node (ref "R17") (pin "2") (pinfunction "2_2") (pintype "passive"))
      (node (ref "U5") (pin "2") (pinfunction "EN_2") (pintype "passive"))
    )
    (net (code "90") (name "Net-(U5-FB)") (class "Default")
      (node (ref "R15") (pin "1") (pinfunction "1_1") (pintype "passive"))
      (node (ref "U5") (pin "1") (pinfunction "FB_1") (pintype "passive"))
      (node (ref "VR1") (pin "3") (pinfunction "W_3") (pintype "passive"))
    )
    (net (code "91") (name "Net-(U5-OCSET)") (class "Default")
      (node (ref "R16") (pin "1") (pinfunction "1_1") (pintype "passive"))
      (node (ref "U5") (pin "3") (pinfunction "OCSET_3") (pintype "passive"))
    )
    (net (code "92") (name "unconnected-(RP2-Pad1)") (class "Default")
      (node (ref "RP2") (pin "1") (pinfunction "1_1") (pintype "passive+no_connect"))
    )
    (net (code "93") (name "unconnected-(RP2-Pad2)") (class "Default")
      (node (ref "RP2") (pin "2") (pinfunction "2_2") (pintype "passive+no_connect"))
    )
    (net (code "94") (name "unconnected-(RP2-Pad7)") (class "Default")
      (node (ref "RP2") (pin "7") (pinfunction "7_7") (pintype "passive+no_connect"))
    )
    (net (code "95") (name "unconnected-(RP2-Pad8)") (class "Default")
      (node (ref "RP2") (pin "8") (pinfunction "8_8") (pintype "passive+no_connect"))
    )
    (net (code "96") (name "unconnected-(S1-Pad3)") (class "Default")
      (node (ref "S1") (pin "3") (pinfunction "3_3") (pintype "passive"))
    )
    (net (code "97") (name "unconnected-(U1-A3-Pad5)") (class "Default")
      (node (ref "U1") (pin "5") (pinfunction "A3_5") (pintype "passive+no_connect"))
    )
    (net (code "98") (name "unconnected-(U1-A6-Pad13)") (class "Default")
      (node (ref "U1") (pin "13") (pinfunction "A6_13") (pintype "passive+no_connect"))
    )
    (net (code "99") (name "unconnected-(U1-Y3-Pad6)") (class "Default")
      (node (ref "U1") (pin "6") (pinfunction "Y3_6") (pintype "passive+no_connect"))
    )
    (net (code "100") (name "unconnected-(U1-Y6-Pad12)") (class "Default")
      (node (ref "U1") (pin "12") (pinfunction "Y6_12") (pintype "passive+no_connect"))
    )
    (net (code "101") (name "unconnected-(U2-3V3-Pad89)") (class "Default")
      (node (ref "U2") (pin "89") (pinfunction "3V3_89") (pintype "passive+no_connect"))
    )
    (net (code "102") (name "unconnected-(U2-3V3-Pad91)") (class "Default")
      (node (ref "U2") (pin "91") (pinfunction "3V3_91") (pintype "passive+no_connect"))
    )
    (net (code "103") (name "unconnected-(U2-B13-Pad23)") (class "Default")
      (node (ref "U2") (pin "23") (pinfunction "B13_23") (pintype "passive+no_connect"))
    )
    (net (code "104") (name "unconnected-(U2-B14-Pad22)") (class "Default")
      (node (ref "U2") (pin "22") (pinfunction "B14_22") (pintype "passive+no_connect"))
    )
    (net (code "105") (name "unconnected-(U2-B16-Pad20)") (class "Default")
      (node (ref "U2") (pin "20") (pinfunction "B16_20") (pintype "passive+no_connect"))
    )
    (net (code "106") (name "unconnected-(U2-B28-Pad8)") (class "Default")
      (node (ref "U2") (pin "8") (pinfunction "B28_8") (pintype "passive+no_connect"))
    )
    (net (code "107") (name "unconnected-(U2-C7-Pad69)") (class "Default")
      (node (ref "U2") (pin "69") (pinfunction "C7_69") (pintype "passive+no_connect"))
    )
    (net (code "108") (name "unconnected-(U2-C8-Pad68)") (class "Default")
      (node (ref "U2") (pin "68") (pinfunction "C8_68") (pintype "passive+no_connect"))
    )
    (net (code "109") (name "unconnected-(U2-C9-Pad67)") (class "Default")
      (node (ref "U2") (pin "67") (pinfunction "C9_67") (pintype "passive+no_connect"))
    )
    (net (code "110") (name "unconnected-(U2-C11-Pad65)") (class "Default")
      (node (ref "U2") (pin "65") (pinfunction "C11_65") (pintype "passive+no_connect"))
    )
    (net (code "111") (name "unconnected-(U2-C14-Pad62)") (class "Default")
      (node (ref "U2") (pin "62") (pinfunction "C14_62") (pintype "passive+no_connect"))
    )
    (net (code "112") (name "unconnected-(U2-C15-Pad61)") (class "Default")
      (node (ref "U2") (pin "61") (pinfunction "C15_61") (pintype "passive+no_connect"))
    )
    (net (code "113") (name "unconnected-(U2-C16-Pad60)") (class "Default")
      (node (ref "U2") (pin "60") (pinfunction "C16_60") (pintype "passive+no_connect"))
    )
    (net (code "114") (name "unconnected-(U2-C17-Pad59)") (class "Default")
      (node (ref "U2") (pin "59") (pinfunction "C17_59") (pintype "passive+no_connect"))
    )
    (net (code "115") (name "unconnected-(U2-C18-Pad58)") (class "Default")
      (node (ref "U2") (pin "58") (pinfunction "C18_58") (pintype "passive+no_connect"))
    )
    (net (code "116") (name "unconnected-(U2-C19-Pad57)") (class "Default")
      (node (ref "U2") (pin "57") (pinfunction "C19_57") (pintype "passive+no_connect"))
    )
    (net (code "117") (name "unconnected-(U2-C20-Pad56)") (class "Default")
      (node (ref "U2") (pin "56") (pinfunction "C20_56") (pintype "passive+no_connect"))
    )
    (net (code "118") (name "unconnected-(U2-C21-Pad55)") (class "Default")
      (node (ref "U2") (pin "55") (pinfunction "C21_55") (pintype "passive+no_connect"))
    )
    (net (code "119") (name "unconnected-(U2-C22-Pad54)") (class "Default")
      (node (ref "U2") (pin "54") (pinfunction "C22_54") (pintype "passive+no_connect"))
    )
    (net (code "120") (name "unconnected-(U2-C23-Pad53)") (class "Default")
      (node (ref "U2") (pin "53") (pinfunction "C23_53") (pintype "passive+no_connect"))
    )
    (net (code "121") (name "unconnected-(U2-C24-Pad52)") (class "Default")
      (node (ref "U2") (pin "52") (pinfunction "C24_52") (pintype "passive+no_connect"))
    )
    (net (code "122") (name "unconnected-(U2-C25-Pad51)") (class "Default")
      (node (ref "U2") (pin "51") (pinfunction "C25_51") (pintype "passive+no_connect"))
    )
    (net (code "123") (name "unconnected-(U2-C26-Pad50)") (class "Default")
      (node (ref "U2") (pin "50") (pinfunction "C26_50") (pintype "passive+no_connect"))
    )
    (net (code "124") (name "unconnected-(U2-C27-Pad49)") (class "Default")
      (node (ref "U2") (pin "49") (pinfunction "C27_49") (pintype "passive+no_connect"))
    )
    (net (code "125") (name "unconnected-(U2-D0-Pad44)") (class "Default")
      (node (ref "U2") (pin "44") (pinfunction "D0_44") (pintype "passive+no_connect"))
    )
    (net (code "126") (name "unconnected-(U2-D1-Pad43)") (class "Default")
      (node (ref "U2") (pin "43") (pinfunction "D1_43") (pintype "passive+no_connect"))
    )
    (net (code "127") (name "unconnected-(U2-D2-Pad42)") (class "Default")
      (node (ref "U2") (pin "42") (pinfunction "D2_42") (pintype "passive+no_connect"))
    )
    (net (code "128") (name "unconnected-(U2-D3-Pad41)") (class "Default")
      (node (ref "U2") (pin "41") (pinfunction "D3_41") (pintype "passive+no_connect"))
    )
    (net (code "129") (name "unconnected-(U2-D18-Pad83)") (class "Default")
      (node (ref "U2") (pin "83") (pinfunction "D18_83") (pintype "passive+no_connect"))
    )
    (net (code "130") (name "unconnected-(U2-D24-Pad77)") (class "Default")
      (node (ref "U2") (pin "77") (pinfunction "D24_77") (pintype "passive+no_connect"))
    )
    (net (code "131") (name "unconnected-(VR1-Pad1)") (class "Default")
      (node (ref "VR1") (pin "1") (pinfunction "1_1") (pintype "passive"))
    )
  )
)
